# bodeplotter_v1.net
KiCad netlist of a schematic drawn in EAGLE
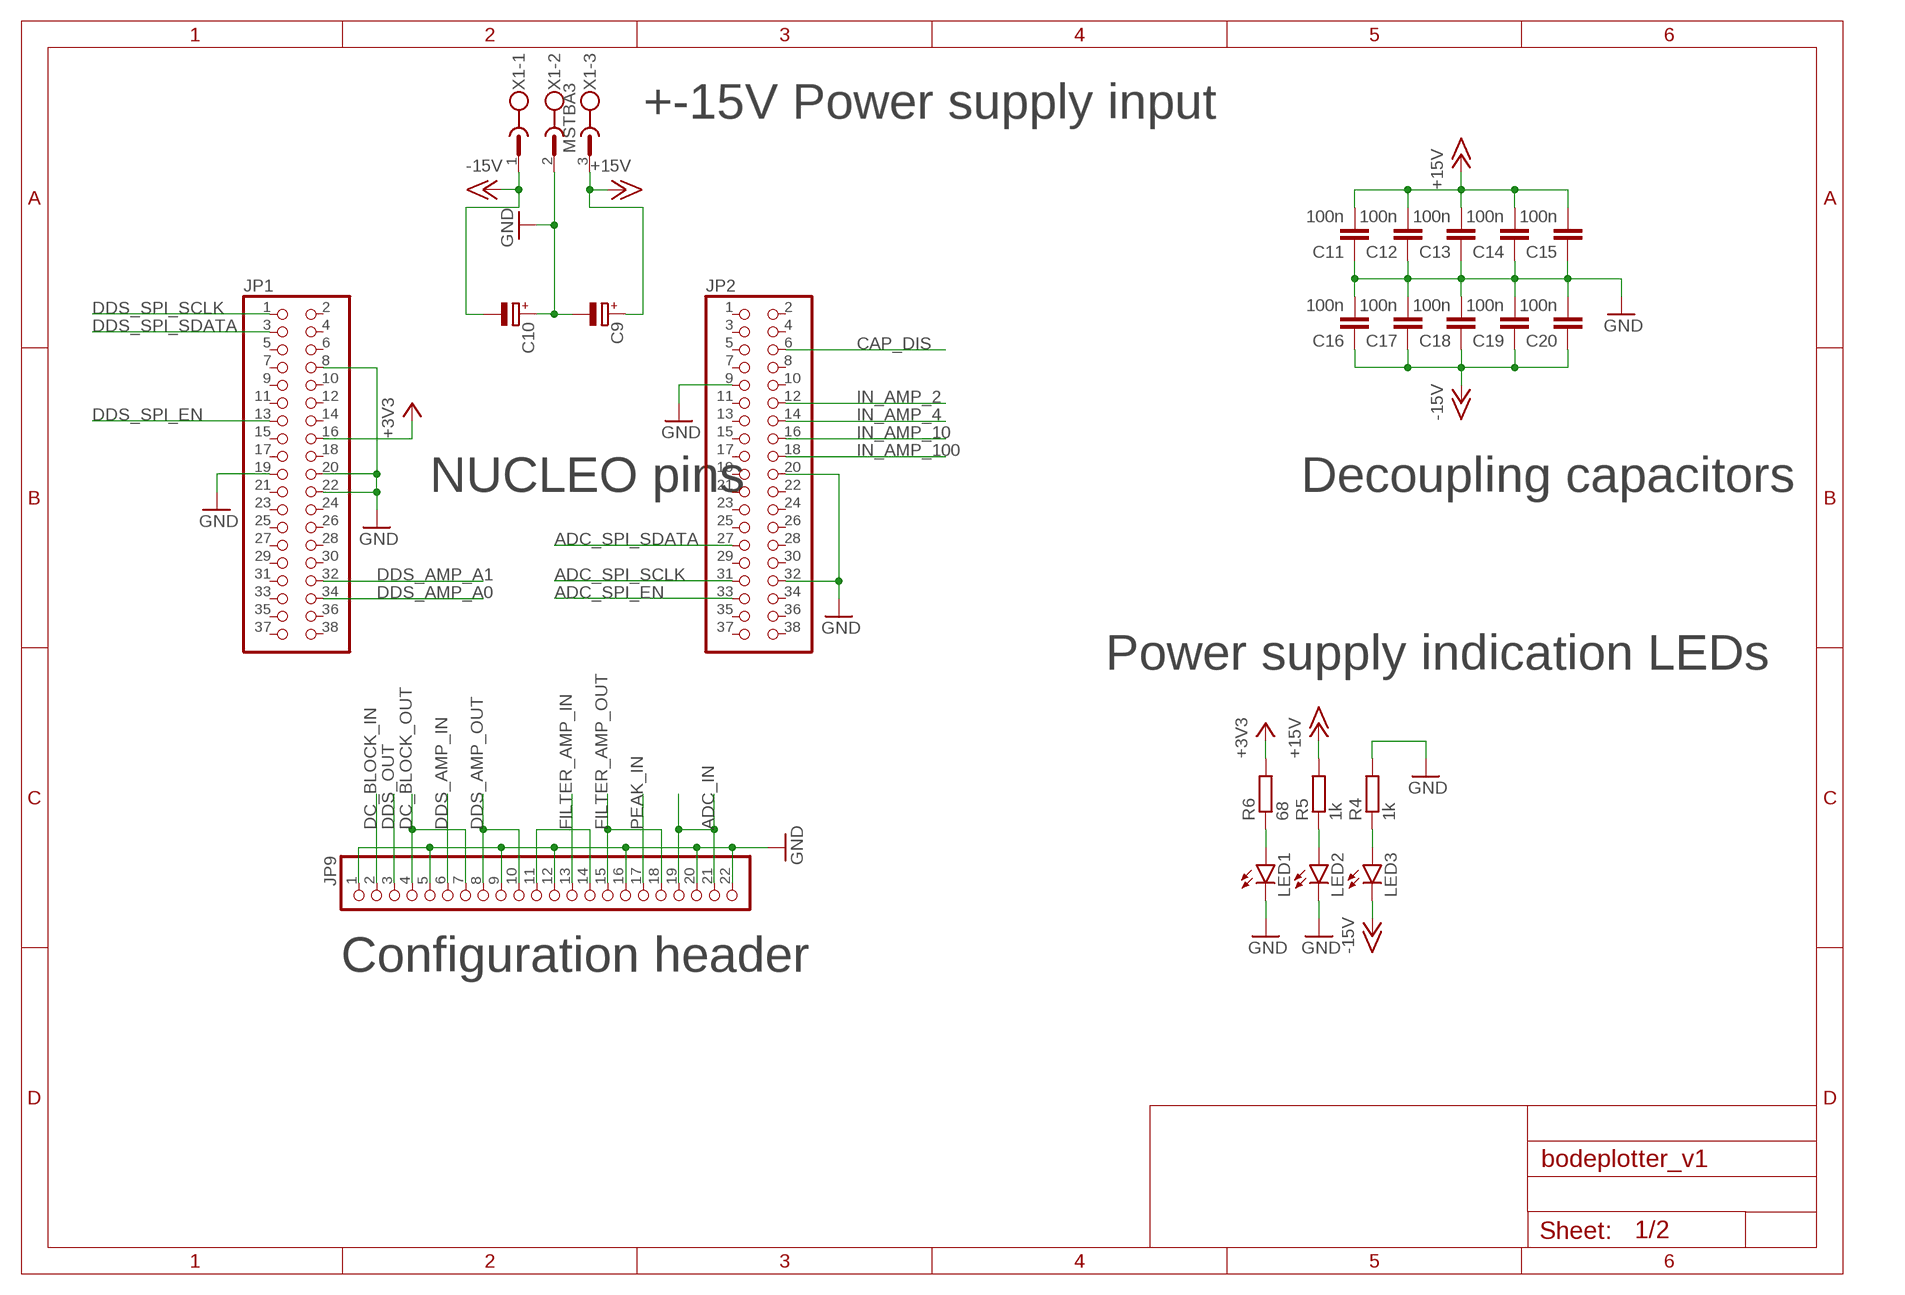
[diagram p0: schematic, sheet 1]
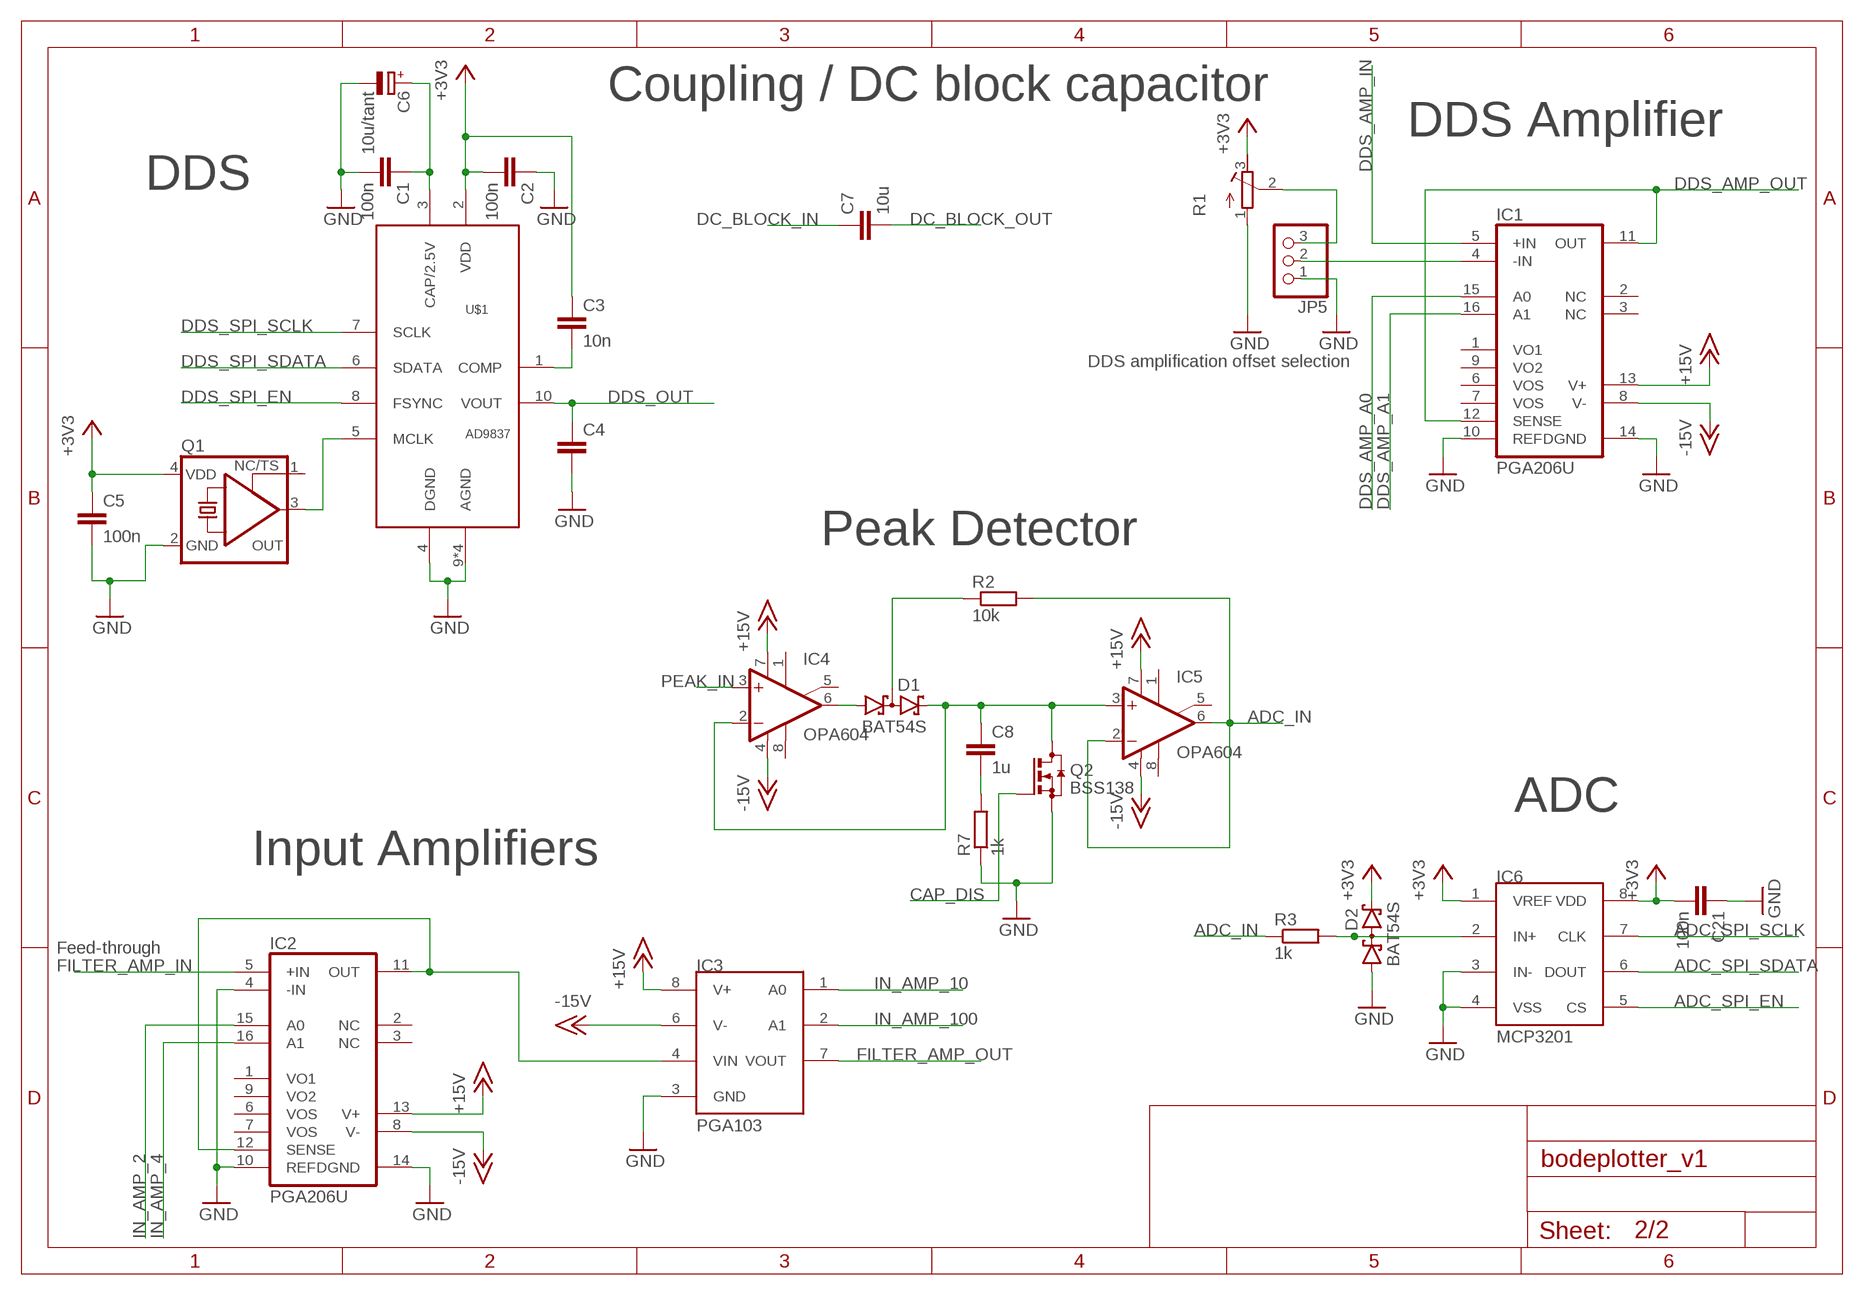
[diagram p1: schematic, sheet 2]

(export (version "E")
  (design (tool "Eeschema 10.0.6"))
  (components
    (comp (ref "C1")
      (value "100n")
      (footprint "eagle-import:C0805")
      (libsource (lib "eagle-import") (part "C-EUC0805"))
    )
    (comp (ref "C2")
      (value "100n")
      (footprint "eagle-import:C0805")
      (libsource (lib "eagle-import") (part "C-EUC0805"))
    )
    (comp (ref "C3")
      (value "10n")
      (footprint "eagle-import:C0805")
      (libsource (lib "eagle-import") (part "C-EUC0805"))
    )
    (comp (ref "C4")
      (value "C-EUC0805")
      (footprint "eagle-import:C0805")
      (libsource (lib "eagle-import") (part "C-EUC0805"))
    )
    (comp (ref "C5")
      (value "100n")
      (footprint "eagle-import:C0805")
      (libsource (lib "eagle-import") (part "C-EUC0805"))
    )
    (comp (ref "C6")
      (value "10u/tant")
      (footprint "eagle-import:CT6032")
      (libsource (lib "eagle-import") (part "CPOL-EUCT6032"))
    )
    (comp (ref "C7")
      (value "10u")
      (footprint "eagle-import:C0805")
      (libsource (lib "eagle-import") (part "C-EUC0805"))
    )
    (comp (ref "C8")
      (value "1u")
      (footprint "eagle-import:C0805")
      (libsource (lib "eagle-import") (part "C-EUC0805"))
    )
    (comp (ref "C21")
      (value "100n")
      (footprint "eagle-import:C0805")
      (libsource (lib "eagle-import") (part "C-EUC0805"))
    )
    (comp (ref "D1")
      (value "BAT54S")
      (footprint "eagle-import:SOT23")
      (libsource (lib "eagle-import") (part "BAT54S"))
    )
    (comp (ref "D2")
      (value "BAT54S")
      (footprint "eagle-import:SOT23")
      (libsource (lib "eagle-import") (part "BAT54S"))
    )
    (comp (ref "IC1")
      (value "PGA206U")
      (footprint "eagle-import:SO16-1")
      (fields (field (name "MF") "TEXAS INSTRUMENTS") (field (name "MPN") "PGA206UA"))
      (libsource (lib "eagle-import") (part "PGA206U"))
    )
    (comp (ref "IC2")
      (value "PGA206U")
      (footprint "eagle-import:SO16-1")
      (fields (field (name "MF") "TEXAS INSTRUMENTS") (field (name "MPN") "PGA206UA"))
      (libsource (lib "eagle-import") (part "PGA206U"))
    )
    (comp (ref "IC3")
      (value "PGA103")
      (footprint "eagle-import:SOIC8")
      (libsource (lib "eagle-import") (part "PGA103"))
    )
    (comp (ref "IC4")
      (value "OPA604")
      (footprint "eagle-import:DIL08")
      (libsource (lib "eagle-import") (part "OPA606P"))
    )
    (comp (ref "IC5")
      (value "OPA604")
      (footprint "eagle-import:DIL08")
      (libsource (lib "eagle-import") (part "OPA606P"))
    )
    (comp (ref "IC6")
      (value "MCP3201")
      (footprint "eagle-import:SOIC8")
      (libsource (lib "eagle-import") (part "MCP3201"))
    )
    (comp (ref "JP5")
      (value "PINHD-1X3")
      (footprint "eagle-import:1X03")
      (libsource (lib "eagle-import") (part "PINHD-1X3"))
    )
    (comp (ref "Q1")
      (value "KXO-PXO/XO-V95")
      (footprint "eagle-import:2.5X2.0_KXO-V95")
      (libsource (lib "eagle-import") (part "KXO-PXO/XO-V95"))
    )
    (comp (ref "Q2")
      (value "BSS138")
      (footprint "eagle-import:SOT23")
      (libsource (lib "eagle-import") (part "BSS123"))
    )
    (comp (ref "R1")
      (value "R-TRIMM64W")
      (footprint "eagle-import:RTRIM64W")
      (libsource (lib "eagle-import") (part "R-TRIMM64W"))
    )
    (comp (ref "R2")
      (value "10k")
      (footprint "eagle-import:R0805")
      (libsource (lib "eagle-import") (part "R-EU_R0805"))
    )
    (comp (ref "R3")
      (value "1k")
      (footprint "eagle-import:R0805")
      (libsource (lib "eagle-import") (part "R-EU_R0805"))
    )
    (comp (ref "R7")
      (value "1k")
      (footprint "eagle-import:R0805")
      (libsource (lib "eagle-import") (part "R-EU_R0805"))
    )
    (comp (ref "U$1")
      (value "AD9837")
      (footprint "eagle-import:ANALOG_DEVICES_AD5667BCPZ-R2_2")
      (libsource (lib "eagle-import") (part "AD9837"))
    )
    (comp (ref "C9")
      (value "CPOL-EU140CLH-0810")
      (footprint "eagle-import:140CLH-0810")
      (libsource (lib "eagle-import") (part "CPOL-EU140CLH-0810"))
    )
    (comp (ref "C10")
      (value "CPOL-EU140CLH-0810")
      (footprint "eagle-import:140CLH-0810")
      (libsource (lib "eagle-import") (part "CPOL-EU140CLH-0810"))
    )
    (comp (ref "C11")
      (value "100n")
      (footprint "eagle-import:C0805")
      (libsource (lib "eagle-import") (part "C-EUC0805"))
    )
    (comp (ref "C12")
      (value "100n")
      (footprint "eagle-import:C0805")
      (libsource (lib "eagle-import") (part "C-EUC0805"))
    )
    (comp (ref "C13")
      (value "100n")
      (footprint "eagle-import:C0805")
      (libsource (lib "eagle-import") (part "C-EUC0805"))
    )
    (comp (ref "C14")
      (value "100n")
      (footprint "eagle-import:C0805")
      (libsource (lib "eagle-import") (part "C-EUC0805"))
    )
    (comp (ref "C15")
      (value "100n")
      (footprint "eagle-import:C0805")
      (libsource (lib "eagle-import") (part "C-EUC0805"))
    )
    (comp (ref "C16")
      (value "100n")
      (footprint "eagle-import:C0805")
      (libsource (lib "eagle-import") (part "C-EUC0805"))
    )
    (comp (ref "C17")
      (value "100n")
      (footprint "eagle-import:C0805")
      (libsource (lib "eagle-import") (part "C-EUC0805"))
    )
    (comp (ref "C18")
      (value "100n")
      (footprint "eagle-import:C0805")
      (libsource (lib "eagle-import") (part "C-EUC0805"))
    )
    (comp (ref "C19")
      (value "100n")
      (footprint "eagle-import:C0805")
      (libsource (lib "eagle-import") (part "C-EUC0805"))
    )
    (comp (ref "C20")
      (value "100n")
      (footprint "eagle-import:C0805")
      (libsource (lib "eagle-import") (part "C-EUC0805"))
    )
    (comp (ref "JP1")
      (value "PINHD-2X19")
      (footprint "eagle-import:2X19")
      (libsource (lib "eagle-import") (part "PINHD-2X19"))
    )
    (comp (ref "JP2")
      (value "PINHD-2X19")
      (footprint "eagle-import:2X19")
      (libsource (lib "eagle-import") (part "PINHD-2X19"))
    )
    (comp (ref "JP9")
      (value "PINHD-1X22")
      (footprint "eagle-import:1X22")
      (libsource (lib "eagle-import") (part "PINHD-1X22"))
    )
    (comp (ref "LED1")
      (value "LEDCHIPLED_1206")
      (footprint "eagle-import:CHIPLED_1206")
      (libsource (lib "eagle-import") (part "LEDCHIPLED_1206"))
    )
    (comp (ref "LED2")
      (value "LEDCHIPLED_1206")
      (footprint "eagle-import:CHIPLED_1206")
      (libsource (lib "eagle-import") (part "LEDCHIPLED_1206"))
    )
    (comp (ref "LED3")
      (value "LEDCHIPLED_1206")
      (footprint "eagle-import:CHIPLED_1206")
      (libsource (lib "eagle-import") (part "LEDCHIPLED_1206"))
    )
    (comp (ref "R4")
      (value "1k")
      (footprint "eagle-import:R0805")
      (libsource (lib "eagle-import") (part "R-EU_R0805"))
    )
    (comp (ref "R5")
      (value "1k")
      (footprint "eagle-import:R0805")
      (libsource (lib "eagle-import") (part "R-EU_R0805"))
    )
    (comp (ref "R6")
      (value "68")
      (footprint "eagle-import:R0805")
      (libsource (lib "eagle-import") (part "R-EU_R0805"))
    )
    (comp (ref "X1")
      (value "MSTBA3")
      (footprint "eagle-import:MSTBA3")
      (fields (field (name "MF") "FARNELL") (field (name "MPN") "1757255"))
      (libsource (lib "eagle-import") (part "MSTBA3"))
    )
  )
  (nets
    (net (code "1") (name "+3V3") (class "Default")
      (node (ref "C2") (pin "2") (pinfunction "2_2") (pintype "passive"))
      (node (ref "C21") (pin "2") (pinfunction "2_2") (pintype "passive"))
      (node (ref "C3") (pin "1") (pinfunction "1_1") (pintype "passive"))
      (node (ref "C5") (pin "1") (pinfunction "1_1") (pintype "passive"))
      (node (ref "D2") (pin "2") (pinfunction "C2_2") (pintype "passive"))
      (node (ref "IC6") (pin "1") (pinfunction "VREF_1") (pintype "bidirectional"))
      (node (ref "IC6") (pin "8") (pinfunction "VDD_8") (pintype "bidirectional"))
      (node (ref "JP1") (pin "16") (pinfunction "16_16") (pintype "passive"))
      (node (ref "Q1") (pin "4") (pinfunction "VDD_4") (pintype "power_in"))
      (node (ref "R1") (pin "3") (pinfunction "E_3") (pintype "passive"))
      (node (ref "R6") (pin "2") (pinfunction "2_2") (pintype "passive"))
      (node (ref "U$1") (pin "2") (pinfunction "VDD_2") (pintype "bidirectional"))
    )
    (net (code "2") (name "+15V") (class "Default")
      (node (ref "C11") (pin "2") (pinfunction "2_2") (pintype "passive"))
      (node (ref "C12") (pin "2") (pinfunction "2_2") (pintype "passive"))
      (node (ref "C13") (pin "2") (pinfunction "2_2") (pintype "passive"))
      (node (ref "C14") (pin "2") (pinfunction "2_2") (pintype "passive"))
      (node (ref "C15") (pin "2") (pinfunction "2_2") (pintype "passive"))
      (node (ref "C9") (pin "+") (pinfunction "+_+") (pintype "passive"))
      (node (ref "IC1") (pin "13") (pinfunction "V+_13") (pintype "power_in"))
      (node (ref "IC2") (pin "13") (pinfunction "V+_13") (pintype "power_in"))
      (node (ref "IC3") (pin "8") (pinfunction "V+_8") (pintype "bidirectional"))
      (node (ref "IC4") (pin "7") (pinfunction "V+_7") (pintype "power_in"))
      (node (ref "IC5") (pin "7") (pinfunction "V+_7") (pintype "power_in"))
      (node (ref "R5") (pin "2") (pinfunction "2_2") (pintype "passive"))
      (node (ref "X1") (pin "3") (pinfunction "1_3") (pintype "passive"))
    )
    (net (code "3") (name "-15V") (class "Default")
      (node (ref "C10") (pin "-") (pinfunction "-_-") (pintype "passive"))
      (node (ref "C16") (pin "1") (pinfunction "1_1") (pintype "passive"))
      (node (ref "C17") (pin "1") (pinfunction "1_1") (pintype "passive"))
      (node (ref "C18") (pin "1") (pinfunction "1_1") (pintype "passive"))
      (node (ref "C19") (pin "1") (pinfunction "1_1") (pintype "passive"))
      (node (ref "C20") (pin "1") (pinfunction "1_1") (pintype "passive"))
      (node (ref "IC1") (pin "8") (pinfunction "V-_8") (pintype "power_in"))
      (node (ref "IC2") (pin "8") (pinfunction "V-_8") (pintype "power_in"))
      (node (ref "IC3") (pin "6") (pinfunction "V-_6") (pintype "bidirectional"))
      (node (ref "IC4") (pin "4") (pinfunction "V-_4") (pintype "power_in"))
      (node (ref "IC5") (pin "4") (pinfunction "V-_4") (pintype "power_in"))
      (node (ref "LED3") (pin "C") (pinfunction "C_C") (pintype "passive"))
      (node (ref "X1") (pin "1") (pinfunction "1_1") (pintype "passive"))
    )
    (net (code "4") (name "ADC_IN") (class "Default")
      (node (ref "IC5") (pin "2") (pinfunction "-IN_2") (pintype "input"))
      (node (ref "IC5") (pin "6") (pinfunction "OUT_6") (pintype "output"))
      (node (ref "JP9") (pin "19") (pinfunction "19_19") (pintype "passive"))
      (node (ref "JP9") (pin "21") (pinfunction "21_21") (pintype "passive"))
      (node (ref "R2") (pin "2") (pinfunction "2_2") (pintype "passive"))
      (node (ref "R3") (pin "1") (pinfunction "1_1") (pintype "passive"))
    )
    (net (code "5") (name "ADC_SPI_EN") (class "Default")
      (node (ref "IC6") (pin "5") (pinfunction "CS_5") (pintype "bidirectional"))
      (node (ref "JP2") (pin "33") (pinfunction "33_33") (pintype "passive"))
    )
    (net (code "6") (name "ADC_SPI_SCLK") (class "Default")
      (node (ref "IC6") (pin "7") (pinfunction "CLK_7") (pintype "bidirectional"))
      (node (ref "JP2") (pin "31") (pinfunction "31_31") (pintype "passive"))
    )
    (net (code "7") (name "ADC_SPI_SDATA") (class "Default")
      (node (ref "IC6") (pin "6") (pinfunction "DOUT_6") (pintype "bidirectional"))
      (node (ref "JP2") (pin "27") (pinfunction "27_27") (pintype "passive"))
    )
    (net (code "8") (name "CAP_DIS") (class "Default")
      (node (ref "JP2") (pin "6") (pinfunction "6_6") (pintype "passive"))
      (node (ref "Q2") (pin "1") (pinfunction "G_1") (pintype "passive"))
    )
    (net (code "9") (name "DC_BLOCK_IN") (class "Default")
      (node (ref "C7") (pin "1") (pinfunction "1_1") (pintype "passive"))
      (node (ref "JP9") (pin "2") (pinfunction "2_2") (pintype "passive"))
    )
    (net (code "10") (name "DC_BLOCK_OUT") (class "Default")
      (node (ref "C7") (pin "2") (pinfunction "2_2") (pintype "passive"))
      (node (ref "JP9") (pin "4") (pinfunction "4_4") (pintype "passive"))
      (node (ref "JP9") (pin "7") (pinfunction "7_7") (pintype "passive"))
    )
    (net (code "11") (name "DDS_AMP_A0") (class "Default")
      (node (ref "IC1") (pin "15") (pinfunction "A0_15") (pintype "input"))
      (node (ref "JP1") (pin "34") (pinfunction "34_34") (pintype "passive"))
    )
    (net (code "12") (name "DDS_AMP_A1") (class "Default")
      (node (ref "IC1") (pin "16") (pinfunction "A1_16") (pintype "input"))
      (node (ref "JP1") (pin "32") (pinfunction "32_32") (pintype "passive"))
    )
    (net (code "13") (name "DDS_AMP_IN") (class "Default")
      (node (ref "IC1") (pin "5") (pinfunction "+IN_5") (pintype "input"))
      (node (ref "JP9") (pin "6") (pinfunction "6_6") (pintype "passive"))
    )
    (net (code "14") (name "DDS_AMP_OUT") (class "Default")
      (node (ref "IC1") (pin "11") (pinfunction "OUT_11") (pintype "output"))
      (node (ref "IC1") (pin "12") (pinfunction "SENSE_12") (pintype "passive"))
      (node (ref "JP9") (pin "10") (pinfunction "10_10") (pintype "passive"))
      (node (ref "JP9") (pin "8") (pinfunction "8_8") (pintype "passive"))
    )
    (net (code "15") (name "DDS_OUT") (class "Default")
      (node (ref "C4") (pin "1") (pinfunction "1_1") (pintype "passive"))
      (node (ref "JP9") (pin "3") (pinfunction "3_3") (pintype "passive"))
      (node (ref "U$1") (pin "10") (pinfunction "VOUT_10") (pintype "bidirectional"))
    )
    (net (code "16") (name "DDS_SPI_EN") (class "Default")
      (node (ref "JP1") (pin "13") (pinfunction "13_13") (pintype "passive"))
      (node (ref "U$1") (pin "8") (pinfunction "FSYNC_8") (pintype "bidirectional"))
    )
    (net (code "17") (name "DDS_SPI_SCLK") (class "Default")
      (node (ref "JP1") (pin "1") (pinfunction "1_1") (pintype "passive"))
      (node (ref "U$1") (pin "7") (pinfunction "SCLK_7") (pintype "bidirectional"))
    )
    (net (code "18") (name "DDS_SPI_SDATA") (class "Default")
      (node (ref "JP1") (pin "3") (pinfunction "3_3") (pintype "passive"))
      (node (ref "U$1") (pin "6") (pinfunction "SDATA_6") (pintype "bidirectional"))
    )
    (net (code "19") (name "FILTER_AMP_IN") (class "Default")
      (node (ref "IC2") (pin "5") (pinfunction "+IN_5") (pintype "input"))
      (node (ref "JP9") (pin "13") (pinfunction "13_13") (pintype "passive"))
    )
    (net (code "20") (name "FILTER_AMP_OUT") (class "Default")
      (node (ref "IC3") (pin "7") (pinfunction "VOUT_7") (pintype "bidirectional"))
      (node (ref "JP9") (pin "15") (pinfunction "15_15") (pintype "passive"))
      (node (ref "JP9") (pin "18") (pinfunction "18_18") (pintype "passive"))
    )
    (net (code "21") (name "GND") (class "Default")
      (node (ref "C1") (pin "2") (pinfunction "2_2") (pintype "passive"))
      (node (ref "C10") (pin "+") (pinfunction "+_+") (pintype "passive"))
      (node (ref "C11") (pin "1") (pinfunction "1_1") (pintype "passive"))
      (node (ref "C12") (pin "1") (pinfunction "1_1") (pintype "passive"))
      (node (ref "C13") (pin "1") (pinfunction "1_1") (pintype "passive"))
      (node (ref "C14") (pin "1") (pinfunction "1_1") (pintype "passive"))
      (node (ref "C15") (pin "1") (pinfunction "1_1") (pintype "passive"))
      (node (ref "C16") (pin "2") (pinfunction "2_2") (pintype "passive"))
      (node (ref "C17") (pin "2") (pinfunction "2_2") (pintype "passive"))
      (node (ref "C18") (pin "2") (pinfunction "2_2") (pintype "passive"))
      (node (ref "C19") (pin "2") (pinfunction "2_2") (pintype "passive"))
      (node (ref "C2") (pin "1") (pinfunction "1_1") (pintype "passive"))
      (node (ref "C20") (pin "2") (pinfunction "2_2") (pintype "passive"))
      (node (ref "C21") (pin "1") (pinfunction "1_1") (pintype "passive"))
      (node (ref "C4") (pin "2") (pinfunction "2_2") (pintype "passive"))
      (node (ref "C5") (pin "2") (pinfunction "2_2") (pintype "passive"))
      (node (ref "C6") (pin "-") (pinfunction "-_-") (pintype "passive"))
      (node (ref "C9") (pin "-") (pinfunction "-_-") (pintype "passive"))
      (node (ref "D2") (pin "1") (pinfunction "A1_1") (pintype "passive"))
      (node (ref "IC1") (pin "10") (pinfunction "REF_10") (pintype "passive"))
      (node (ref "IC1") (pin "14") (pinfunction "DGND_14") (pintype "power_in"))
      (node (ref "IC2") (pin "10") (pinfunction "REF_10") (pintype "passive"))
      (node (ref "IC2") (pin "14") (pinfunction "DGND_14") (pintype "power_in"))
      (node (ref "IC2") (pin "4") (pinfunction "-IN_4") (pintype "input"))
      (node (ref "IC3") (pin "3") (pinfunction "GND_3") (pintype "bidirectional"))
      (node (ref "IC6") (pin "3") (pinfunction "IN-_3") (pintype "bidirectional"))
      (node (ref "IC6") (pin "4") (pinfunction "VSS_4") (pintype "bidirectional"))
      (node (ref "JP1") (pin "19") (pinfunction "19_19") (pintype "passive"))
      (node (ref "JP1") (pin "20") (pinfunction "20_20") (pintype "passive"))
      (node (ref "JP1") (pin "22") (pinfunction "22_22") (pintype "passive"))
      (node (ref "JP1") (pin "8") (pinfunction "8_8") (pintype "passive"))
      (node (ref "JP2") (pin "20") (pinfunction "20_20") (pintype "passive"))
      (node (ref "JP2") (pin "32") (pinfunction "32_32") (pintype "passive"))
      (node (ref "JP2") (pin "9") (pinfunction "9_9") (pintype "passive"))
      (node (ref "JP5") (pin "1") (pinfunction "1_1") (pintype "passive"))
      (node (ref "JP9") (pin "1") (pinfunction "1_1") (pintype "passive"))
      (node (ref "JP9") (pin "12") (pinfunction "12_12") (pintype "passive"))
      (node (ref "JP9") (pin "16") (pinfunction "16_16") (pintype "passive"))
      (node (ref "JP9") (pin "20") (pinfunction "20_20") (pintype "passive"))
      (node (ref "JP9") (pin "22") (pinfunction "22_22") (pintype "passive"))
      (node (ref "JP9") (pin "5") (pinfunction "5_5") (pintype "passive"))
      (node (ref "JP9") (pin "9") (pinfunction "9_9") (pintype "passive"))
      (node (ref "LED1") (pin "C") (pinfunction "C_C") (pintype "passive"))
      (node (ref "LED2") (pin "C") (pinfunction "C_C") (pintype "passive"))
      (node (ref "Q1") (pin "2") (pinfunction "GND_2") (pintype "power_in"))
      (node (ref "Q2") (pin "2") (pinfunction "S_2") (pintype "passive"))
      (node (ref "R1") (pin "1") (pinfunction "A_1") (pintype "passive"))
      (node (ref "R4") (pin "2") (pinfunction "2_2") (pintype "passive"))
      (node (ref "R7") (pin "1") (pinfunction "1_1") (pintype "passive"))
      (node (ref "U$1") (pin "11") (pinfunction "AGND_11") (pintype "bidirectional"))
      (node (ref "U$1") (pin "4") (pinfunction "DGND_4") (pintype "bidirectional"))
      (node (ref "U$1") (pin "9") (pinfunction "AGND_9") (pintype "bidirectional"))
      (node (ref "U$1") (pin "PAD_1") (pinfunction "AGND_PAD_1") (pintype "bidirectional"))
      (node (ref "U$1") (pin "PAD_2") (pinfunction "AGND_PAD_2") (pintype "bidirectional"))
      (node (ref "X1") (pin "2") (pinfunction "1_2") (pintype "passive"))
    )
    (net (code "22") (name "IN_AMP_2") (class "Default")
      (node (ref "IC2") (pin "15") (pinfunction "A0_15") (pintype "input"))
      (node (ref "JP2") (pin "12") (pinfunction "12_12") (pintype "passive"))
    )
    (net (code "23") (name "IN_AMP_4") (class "Default")
      (node (ref "IC2") (pin "16") (pinfunction "A1_16") (pintype "input"))
      (node (ref "JP2") (pin "14") (pinfunction "14_14") (pintype "passive"))
    )
    (net (code "24") (name "IN_AMP_10") (class "Default")
      (node (ref "IC3") (pin "1") (pinfunction "A0_1") (pintype "bidirectional"))
      (node (ref "JP2") (pin "16") (pinfunction "16_16") (pintype "passive"))
    )
    (net (code "25") (name "IN_AMP_100") (class "Default")
      (node (ref "IC3") (pin "2") (pinfunction "A1_2") (pintype "bidirectional"))
      (node (ref "JP2") (pin "18") (pinfunction "18_18") (pintype "passive"))
    )
    (net (code "26") (name "Net-(C8-Pad2)") (class "Default")
      (node (ref "C8") (pin "2") (pinfunction "2_2") (pintype "passive"))
      (node (ref "R7") (pin "2") (pinfunction "2_2") (pintype "passive"))
    )
    (net (code "27") (name "Net-(D1-A1)") (class "Default")
      (node (ref "D1") (pin "1") (pinfunction "A1_1") (pintype "passive"))
      (node (ref "IC4") (pin "6") (pinfunction "OUT_6") (pintype "output"))
    )
    (net (code "28") (name "Net-(D1-C1A2)") (class "Default")
      (node (ref "D1") (pin "3") (pinfunction "C1A2_3") (pintype "passive"))
      (node (ref "R2") (pin "1") (pinfunction "1_1") (pintype "passive"))
    )
    (net (code "29") (name "Net-(D1-C2)") (class "Default")
      (node (ref "C8") (pin "1") (pinfunction "1_1") (pintype "passive"))
      (node (ref "D1") (pin "2") (pinfunction "C2_2") (pintype "passive"))
      (node (ref "IC4") (pin "2") (pinfunction "-IN_2") (pintype "input"))
      (node (ref "IC5") (pin "3") (pinfunction "+IN_3") (pintype "input"))
      (node (ref "Q2") (pin "3") (pinfunction "D_3") (pintype "passive"))
    )
    (net (code "30") (name "Net-(D2-C1A2)") (class "Default")
      (node (ref "D2") (pin "3") (pinfunction "C1A2_3") (pintype "passive"))
      (node (ref "IC6") (pin "2") (pinfunction "IN+_2") (pintype "bidirectional"))
      (node (ref "R3") (pin "2") (pinfunction "2_2") (pintype "passive"))
    )
    (net (code "31") (name "Net-(IC1--IN)") (class "Default")
      (node (ref "IC1") (pin "4") (pinfunction "-IN_4") (pintype "input"))
      (node (ref "JP5") (pin "2") (pinfunction "2_2") (pintype "passive"))
    )
    (net (code "32") (name "Net-(IC2-OUT)") (class "Default")
      (node (ref "IC2") (pin "11") (pinfunction "OUT_11") (pintype "output"))
      (node (ref "IC2") (pin "12") (pinfunction "SENSE_12") (pintype "passive"))
      (node (ref "IC3") (pin "4") (pinfunction "VIN_4") (pintype "bidirectional"))
    )
    (net (code "33") (name "Net-(JP9-Pad11)") (class "Default")
      (node (ref "JP9") (pin "11") (pinfunction "11_11") (pintype "passive"))
      (node (ref "JP9") (pin "14") (pinfunction "14_14") (pintype "passive"))
    )
    (net (code "34") (name "Net-(LED1-PadA)") (class "Default")
      (node (ref "LED1") (pin "A") (pinfunction "A_A") (pintype "passive"))
      (node (ref "R6") (pin "1") (pinfunction "1_1") (pintype "passive"))
    )
    (net (code "35") (name "Net-(LED2-PadA)") (class "Default")
      (node (ref "LED2") (pin "A") (pinfunction "A_A") (pintype "passive"))
      (node (ref "R5") (pin "1") (pinfunction "1_1") (pintype "passive"))
    )
    (net (code "36") (name "Net-(LED3-PadA)") (class "Default")
      (node (ref "LED3") (pin "A") (pinfunction "A_A") (pintype "passive"))
      (node (ref "R4") (pin "1") (pinfunction "1_1") (pintype "passive"))
    )
    (net (code "37") (name "Net-(Q1-OUT)") (class "Default")
      (node (ref "Q1") (pin "3") (pinfunction "OUT_3") (pintype "output"))
      (node (ref "U$1") (pin "5") (pinfunction "MCLK_5") (pintype "bidirectional"))
    )
    (net (code "38") (name "Net-(R1-S)") (class "Default")
      (node (ref "JP5") (pin "3") (pinfunction "3_3") (pintype "passive"))
      (node (ref "R1") (pin "2") (pinfunction "S_2") (pintype "passive"))
    )
    (net (code "39") (name "Net-(U$1-CAP{slash}2.5V)") (class "Default")
      (node (ref "C1") (pin "1") (pinfunction "1_1") (pintype "passive"))
      (node (ref "C6") (pin "+") (pinfunction "+_+") (pintype "passive"))
      (node (ref "U$1") (pin "3") (pinfunction "CAP/2.5V_3") (pintype "bidirectional"))
    )
    (net (code "40") (name "Net-(U$1-COMP)") (class "Default")
      (node (ref "C3") (pin "2") (pinfunction "2_2") (pintype "passive"))
      (node (ref "U$1") (pin "1") (pinfunction "COMP_1") (pintype "bidirectional"))
    )
    (net (code "41") (name "PEAK_IN") (class "Default")
      (node (ref "IC4") (pin "3") (pinfunction "+IN_3") (pintype "input"))
      (node (ref "JP9") (pin "17") (pinfunction "17_17") (pintype "passive"))
    )
    (net (code "42") (name "unconnected-(IC1-NC-Pad2)") (class "Default")
      (node (ref "IC1") (pin "2") (pinfunction "NC_2") (pintype "no_connect"))
    )
    (net (code "43") (name "unconnected-(IC1-NC-Pad3)") (class "Default")
      (node (ref "IC1") (pin "3") (pinfunction "NC_3") (pintype "no_connect"))
    )
    (net (code "44") (name "unconnected-(IC1-VO1-Pad1)") (class "Default")
      (node (ref "IC1") (pin "1") (pinfunction "VO1_1") (pintype "passive"))
    )
    (net (code "45") (name "unconnected-(IC1-VO2-Pad9)") (class "Default")
      (node (ref "IC1") (pin "9") (pinfunction "VO2_9") (pintype "passive"))
    )
    (net (code "46") (name "unconnected-(IC1-VOS-Pad6)") (class "Default")
      (node (ref "IC1") (pin "6") (pinfunction "VOS_6") (pintype "passive"))
    )
    (net (code "47") (name "unconnected-(IC1-VOS-Pad7)") (class "Default")
      (node (ref "IC1") (pin "7") (pinfunction "VOS_7") (pintype "passive"))
    )
    (net (code "48") (name "unconnected-(IC2-NC-Pad2)") (class "Default")
      (node (ref "IC2") (pin "2") (pinfunction "NC_2") (pintype "no_connect"))
    )
    (net (code "49") (name "unconnected-(IC2-NC-Pad3)") (class "Default")
      (node (ref "IC2") (pin "3") (pinfunction "NC_3") (pintype "no_connect"))
    )
    (net (code "50") (name "unconnected-(IC2-VO1-Pad1)") (class "Default")
      (node (ref "IC2") (pin "1") (pinfunction "VO1_1") (pintype "passive"))
    )
    (net (code "51") (name "unconnected-(IC2-VO2-Pad9)") (class "Default")
      (node (ref "IC2") (pin "9") (pinfunction "VO2_9") (pintype "passive"))
    )
    (net (code "52") (name "unconnected-(IC2-VOS-Pad6)") (class "Default")
      (node (ref "IC2") (pin "6") (pinfunction "VOS_6") (pintype "passive"))
    )
    (net (code "53") (name "unconnected-(IC2-VOS-Pad7)") (class "Default")
      (node (ref "IC2") (pin "7") (pinfunction "VOS_7") (pintype "passive"))
    )
    (net (code "54") (name "unconnected-(IC4-ON1-Pad1)") (class "Default")
      (node (ref "IC4") (pin "1") (pinfunction "ON1_1") (pintype "passive"))
    )
    (net (code "55") (name "unconnected-(IC4-ON2-Pad5)") (class "Default")
      (node (ref "IC4") (pin "5") (pinfunction "ON2_5") (pintype "passive"))
    )
    (net (code "56") (name "unconnected-(IC4-OPT-Pad8)") (class "Default")
      (node (ref "IC4") (pin "8") (pinfunction "OPT_8") (pintype "passive"))
    )
    (net (code "57") (name "unconnected-(IC5-ON1-Pad1)") (class "Default")
      (node (ref "IC5") (pin "1") (pinfunction "ON1_1") (pintype "passive"))
    )
    (net (code "58") (name "unconnected-(IC5-ON2-Pad5)") (class "Default")
      (node (ref "IC5") (pin "5") (pinfunction "ON2_5") (pintype "passive"))
    )
    (net (code "59") (name "unconnected-(IC5-OPT-Pad8)") (class "Default")
      (node (ref "IC5") (pin "8") (pinfunction "OPT_8") (pintype "passive"))
    )
    (net (code "60") (name "unconnected-(JP1-Pad2)") (class "Default")
      (node (ref "JP1") (pin "2") (pinfunction "2_2") (pintype "passive"))
    )
    (net (code "61") (name "unconnected-(JP1-Pad4)") (class "Default")
      (node (ref "JP1") (pin "4") (pinfunction "4_4") (pintype "passive"))
    )
    (net (code "62") (name "unconnected-(JP1-Pad5)") (class "Default")
      (node (ref "JP1") (pin "5") (pinfunction "5_5") (pintype "passive"))
    )
    (net (code "63") (name "unconnected-(JP1-Pad6)") (class "Default")
      (node (ref "JP1") (pin "6") (pinfunction "6_6") (pintype "passive"))
    )
    (net (code "64") (name "unconnected-(JP1-Pad7)") (class "Default")
      (node (ref "JP1") (pin "7") (pinfunction "7_7") (pintype "passive"))
    )
    (net (code "65") (name "unconnected-(JP1-Pad9)") (class "Default")
      (node (ref "JP1") (pin "9") (pinfunction "9_9") (pintype "passive"))
    )
    (net (code "66") (name "unconnected-(JP1-Pad10)") (class "Default")
      (node (ref "JP1") (pin "10") (pinfunction "10_10") (pintype "passive"))
    )
    (net (code "67") (name "unconnected-(JP1-Pad11)") (class "Default")
      (node (ref "JP1") (pin "11") (pinfunction "11_11") (pintype "passive"))
    )
    (net (code "68") (name "unconnected-(JP1-Pad12)") (class "Default")
      (node (ref "JP1") (pin "12") (pinfunction "12_12") (pintype "passive"))
    )
    (net (code "69") (name "unconnected-(JP1-Pad14)") (class "Default")
      (node (ref "JP1") (pin "14") (pinfunction "14_14") (pintype "passive"))
    )
    (net (code "70") (name "unconnected-(JP1-Pad15)") (class "Default")
      (node (ref "JP1") (pin "15") (pinfunction "15_15") (pintype "passive"))
    )
    (net (code "71") (name "unconnected-(JP1-Pad17)") (class "Default")
      (node (ref "JP1") (pin "17") (pinfunction "17_17") (pintype "passive"))
    )
    (net (code "72") (name "unconnected-(JP1-Pad18)") (class "Default")
      (node (ref "JP1") (pin "18") (pinfunction "18_18") (pintype "passive"))
    )
    (net (code "73") (name "unconnected-(JP1-Pad21)") (class "Default")
      (node (ref "JP1") (pin "21") (pinfunction "21_21") (pintype "passive"))
    )
    (net (code "74") (name "unconnected-(JP1-Pad23)") (class "Default")
      (node (ref "JP1") (pin "23") (pinfunction "23_23") (pintype "passive"))
    )
    (net (code "75") (name "unconnected-(JP1-Pad24)") (class "Default")
      (node (ref "JP1") (pin "24") (pinfunction "24_24") (pintype "passive"))
    )
    (net (code "76") (name "unconnected-(JP1-Pad25)") (class "Default")
      (node (ref "JP1") (pin "25") (pinfunction "25_25") (pintype "passive"))
    )
    (net (code "77") (name "unconnected-(JP1-Pad26)") (class "Default")
      (node (ref "JP1") (pin "26") (pinfunction "26_26") (pintype "passive"))
    )
    (net (code "78") (name "unconnected-(JP1-Pad27)") (class "Default")
      (node (ref "JP1") (pin "27") (pinfunction "27_27") (pintype "passive"))
    )
    (net (code "79") (name "unconnected-(JP1-Pad28)") (class "Default")
      (node (ref "JP1") (pin "28") (pinfunction "28_28") (pintype "passive"))
    )
    (net (code "80") (name "unconnected-(JP1-Pad29)") (class "Default")
      (node (ref "JP1") (pin "29") (pinfunction "29_29") (pintype "passive"))
    )
    (net (code "81") (name "unconnected-(JP1-Pad30)") (class "Default")
      (node (ref "JP1") (pin "30") (pinfunction "30_30") (pintype "passive"))
    )
    (net (code "82") (name "unconnected-(JP1-Pad31)") (class "Default")
      (node (ref "JP1") (pin "31") (pinfunction "31_31") (pintype "passive"))
    )
    (net (code "83") (name "unconnected-(JP1-Pad33)") (class "Default")
      (node (ref "JP1") (pin "33") (pinfunction "33_33") (pintype "passive"))
    )
    (net (code "84") (name "unconnected-(JP1-Pad35)") (class "Default")
      (node (ref "JP1") (pin "35") (pinfunction "35_35") (pintype "passive"))
    )
    (net (code "85") (name "unconnected-(JP1-Pad36)") (class "Default")
      (node (ref "JP1") (pin "36") (pinfunction "36_36") (pintype "passive"))
    )
    (net (code "86") (name "unconnected-(JP1-Pad37)") (class "Default")
      (node (ref "JP1") (pin "37") (pinfunction "37_37") (pintype "passive"))
    )
    (net (code "87") (name "unconnected-(JP1-Pad38)") (class "Default")
      (node (ref "JP1") (pin "38") (pinfunction "38_38") (pintype "passive"))
    )
    (net (code "88") (name "unconnected-(JP2-Pad1)") (class "Default")
      (node (ref "JP2") (pin "1") (pinfunction "1_1") (pintype "passive"))
    )
    (net (code "89") (name "unconnected-(JP2-Pad2)") (class "Default")
      (node (ref "JP2") (pin "2") (pinfunction "2_2") (pintype "passive"))
    )
    (net (code "90") (name "unconnected-(JP2-Pad3)") (class "Default")
      (node (ref "JP2") (pin "3") (pinfunction "3_3") (pintype "passive"))
    )
    (net (code "91") (name "unconnected-(JP2-Pad4)") (class "Default")
      (node (ref "JP2") (pin "4") (pinfunction "4_4") (pintype "passive"))
    )
    (net (code "92") (name "unconnected-(JP2-Pad5)") (class "Default")
      (node (ref "JP2") (pin "5") (pinfunction "5_5") (pintype "passive"))
    )
    (net (code "93") (name "unconnected-(JP2-Pad7)") (class "Default")
      (node (ref "JP2") (pin "7") (pinfunction "7_7") (pintype "passive"))
    )
    (net (code "94") (name "unconnected-(JP2-Pad8)") (class "Default")
      (node (ref "JP2") (pin "8") (pinfunction "8_8") (pintype "passive"))
    )
    (net (code "95") (name "unconnected-(JP2-Pad10)") (class "Default")
      (node (ref "JP2") (pin "10") (pinfunction "10_10") (pintype "passive"))
    )
    (net (code "96") (name "unconnected-(JP2-Pad11)") (class "Default")
      (node (ref "JP2") (pin "11") (pinfunction "11_11") (pintype "passive"))
    )
    (net (code "97") (name "unconnected-(JP2-Pad13)") (class "Default")
      (node (ref "JP2") (pin "13") (pinfunction "13_13") (pintype "passive"))
    )
    (net (code "98") (name "unconnected-(JP2-Pad15)") (class "Default")
      (node (ref "JP2") (pin "15") (pinfunction "15_15") (pintype "passive"))
    )
    (net (code "99") (name "unconnected-(JP2-Pad17)") (class "Default")
      (node (ref "JP2") (pin "17") (pinfunction "17_17") (pintype "passive"))
    )
    (net (code "100") (name "unconnected-(JP2-Pad19)") (class "Default")
      (node (ref "JP2") (pin "19") (pinfunction "19_19") (pintype "passive"))
    )
    (net (code "101") (name "unconnected-(JP2-Pad21)") (class "Default")
      (node (ref "JP2") (pin "21") (pinfunction "21_21") (pintype "passive"))
    )
    (net (code "102") (name "unconnected-(JP2-Pad22)") (class "Default")
      (node (ref "JP2") (pin "22") (pinfunction "22_22") (pintype "passive"))
    )
    (net (code "103") (name "unconnected-(JP2-Pad23)") (class "Default")
      (node (ref "JP2") (pin "23") (pinfunction "23_23") (pintype "passive"))
    )
    (net (code "104") (name "unconnected-(JP2-Pad24)") (class "Default")
      (node (ref "JP2") (pin "24") (pinfunction "24_24") (pintype "passive"))
    )
    (net (code "105") (name "unconnected-(JP2-Pad25)") (class "Default")
      (node (ref "JP2") (pin "25") (pinfunction "25_25") (pintype "passive"))
    )
    (net (code "106") (name "unconnected-(JP2-Pad26)") (class "Default")
      (node (ref "JP2") (pin "26") (pinfunction "26_26") (pintype "passive"))
    )
    (net (code "107") (name "unconnected-(JP2-Pad28)") (class "Default")
      (node (ref "JP2") (pin "28") (pinfunction "28_28") (pintype "passive"))
    )
    (net (code "108") (name "unconnected-(JP2-Pad29)") (class "Default")
      (node (ref "JP2") (pin "29") (pinfunction "29_29") (pintype "passive"))
    )
    (net (code "109") (name "unconnected-(JP2-Pad30)") (class "Default")
      (node (ref "JP2") (pin "30") (pinfunction "30_30") (pintype "passive"))
    )
    (net (code "110") (name "unconnected-(JP2-Pad34)") (class "Default")
      (node (ref "JP2") (pin "34") (pinfunction "34_34") (pintype "passive"))
    )
    (net (code "111") (name "unconnected-(JP2-Pad35)") (class "Default")
      (node (ref "JP2") (pin "35") (pinfunction "35_35") (pintype "passive"))
    )
    (net (code "112") (name "unconnected-(JP2-Pad36)") (class "Default")
      (node (ref "JP2") (pin "36") (pinfunction "36_36") (pintype "passive"))
    )
    (net (code "113") (name "unconnected-(JP2-Pad37)") (class "Default")
      (node (ref "JP2") (pin "37") (pinfunction "37_37") (pintype "passive"))
    )
    (net (code "114") (name "unconnected-(JP2-Pad38)") (class "Default")
      (node (ref "JP2") (pin "38") (pinfunction "38_38") (pintype "passive"))
    )
    (net (code "115") (name "unconnected-(Q1-TS-Pad1)") (class "Default")
      (node (ref "Q1") (pin "1") (pinfunction "TS_1") (pintype "passive"))
    )
  )
)
